# IO.net
KiCad netlist of a schematic drawn in Altium Designer
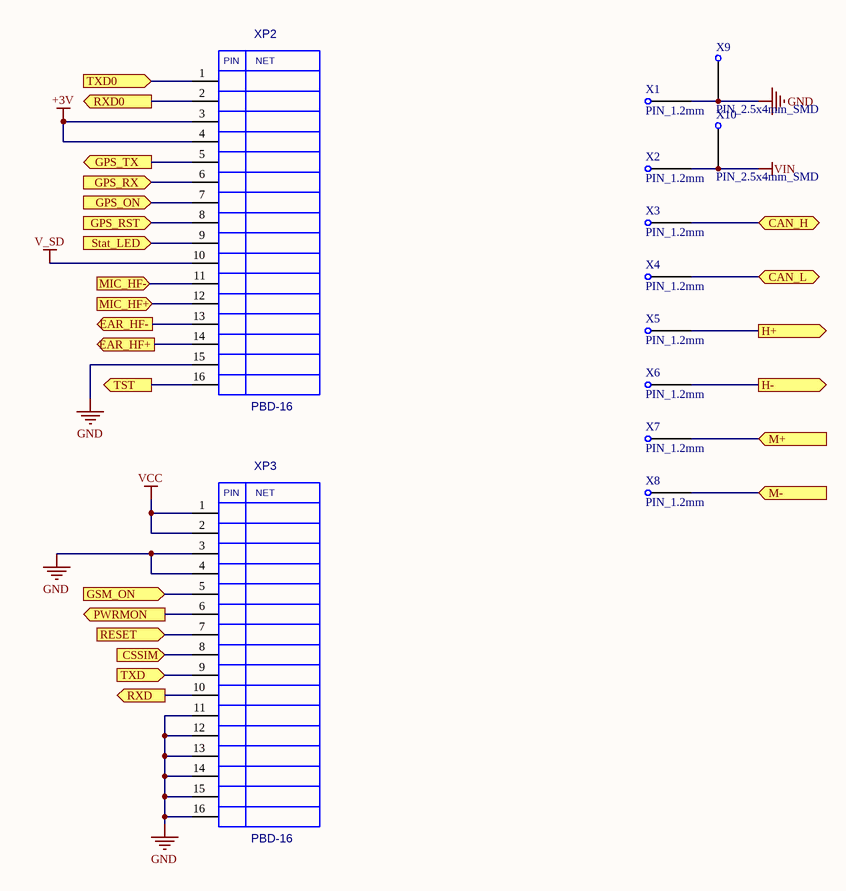
[diagram p0: IO.SchDoc]

(export (version "E")
  (design (tool "Eeschema 10.0.6"))
  (components
    (comp (ref "X1")
      (value "PIN_1.2mm")
      (footprint "PIN_1.2mm")
      (libsource (lib "gprs_modem_2") (part "PIN_1.2mm"))
    )
    (comp (ref "X2")
      (value "PIN_1.2mm")
      (footprint "PIN_1.2mm")
      (libsource (lib "gprs_modem_2") (part "PIN_1.2mm"))
    )
    (comp (ref "X3")
      (value "PIN_1.2mm")
      (footprint "PIN_1.2mm")
      (libsource (lib "gprs_modem_2") (part "PIN_1.2mm"))
    )
    (comp (ref "X4")
      (value "PIN_1.2mm")
      (footprint "PIN_1.2mm")
      (libsource (lib "gprs_modem_2") (part "PIN_1.2mm"))
    )
    (comp (ref "X5")
      (value "PIN_1.2mm")
      (footprint "PIN_1.2mm")
      (libsource (lib "gprs_modem_2") (part "PIN_1.2mm"))
    )
    (comp (ref "X6")
      (value "PIN_1.2mm")
      (footprint "PIN_1.2mm")
      (libsource (lib "gprs_modem_2") (part "PIN_1.2mm"))
    )
    (comp (ref "X7")
      (value "PIN_1.2mm")
      (footprint "PIN_1.2mm")
      (libsource (lib "gprs_modem_2") (part "PIN_1.2mm"))
    )
    (comp (ref "X8")
      (value "PIN_1.2mm")
      (footprint "PIN_1.2mm")
      (libsource (lib "gprs_modem_2") (part "PIN_1.2mm"))
    )
    (comp (ref "X9")
      (value "PIN_2.5x4mm_SMD")
      (footprint "PIN_2.5x4mm_SMD")
      (libsource (lib "gprs_modem_2") (part "PIN_2.5x4mm_SMD"))
    )
    (comp (ref "X10")
      (value "PIN_2.5x4mm_SMD")
      (footprint "PIN_2.5x4mm_SMD")
      (libsource (lib "gprs_modem_2") (part "PIN_2.5x4mm_SMD"))
    )
    (comp (ref "XP2") (value "PBD-16") (footprint "PBD16") (libsource (lib "gprs_modem") (part "PBD-16")))
    (comp (ref "XP3") (value "PBD-16") (footprint "PBD16") (libsource (lib "gprs_modem") (part "PBD-16")))
  )
  (nets
    (net (code "1") (name "+3V") (class "Default")
      (node (ref "XP2") (pin "3") (pinfunction "3_3") (pintype "passive"))
      (node (ref "XP2") (pin "4") (pinfunction "4_4") (pintype "passive"))
    )
    (net (code "2") (name "/CAN_H") (class "Default")
      (node (ref "X3") (pin "1") (pinfunction "1_1") (pintype "passive"))
    )
    (net (code "3") (name "/CAN_L") (class "Default")
      (node (ref "X4") (pin "1") (pinfunction "1_1") (pintype "passive"))
    )
    (net (code "4") (name "/CSSIM") (class "Default")
      (node (ref "XP3") (pin "8") (pinfunction "8_8") (pintype "passive"))
    )
    (net (code "5") (name "/EAR_HF+") (class "Default")
      (node (ref "XP2") (pin "14") (pinfunction "14_14") (pintype "passive"))
    )
    (net (code "6") (name "/EAR_HF-") (class "Default")
      (node (ref "XP2") (pin "13") (pinfunction "13_13") (pintype "passive"))
    )
    (net (code "7") (name "/GPS_ON") (class "Default")
      (node (ref "XP2") (pin "7") (pinfunction "7_7") (pintype "passive"))
    )
    (net (code "8") (name "/GPS_RST") (class "Default")
      (node (ref "XP2") (pin "8") (pinfunction "8_8") (pintype "passive"))
    )
    (net (code "9") (name "/GPS_RX") (class "Default")
      (node (ref "XP2") (pin "6") (pinfunction "6_6") (pintype "passive"))
    )
    (net (code "10") (name "/GPS_TX") (class "Default")
      (node (ref "XP2") (pin "5") (pinfunction "5_5") (pintype "passive"))
    )
    (net (code "11") (name "/GSM_ON") (class "Default")
      (node (ref "XP3") (pin "5") (pinfunction "5_5") (pintype "passive"))
    )
    (net (code "12") (name "/H+") (class "Default")
      (node (ref "X5") (pin "1") (pinfunction "1_1") (pintype "passive"))
    )
    (net (code "13") (name "/H-") (class "Default")
      (node (ref "X6") (pin "1") (pinfunction "1_1") (pintype "passive"))
    )
    (net (code "14") (name "/M+") (class "Default")
      (node (ref "X7") (pin "1") (pinfunction "1_1") (pintype "passive"))
    )
    (net (code "15") (name "/M-") (class "Default")
      (node (ref "X8") (pin "1") (pinfunction "1_1") (pintype "passive"))
    )
    (net (code "16") (name "/MIC_HF+") (class "Default")
      (node (ref "XP2") (pin "12") (pinfunction "12_12") (pintype "passive"))
    )
    (net (code "17") (name "/MIC_HF-") (class "Default")
      (node (ref "XP2") (pin "11") (pinfunction "11_11") (pintype "passive"))
    )
    (net (code "18") (name "/PWRMON") (class "Default")
      (node (ref "XP3") (pin "6") (pinfunction "6_6") (pintype "passive"))
    )
    (net (code "19") (name "/RESET") (class "Default")
      (node (ref "XP3") (pin "7") (pinfunction "7_7") (pintype "passive"))
    )
    (net (code "20") (name "/RXD") (class "Default")
      (node (ref "XP3") (pin "10") (pinfunction "10_10") (pintype "passive"))
    )
    (net (code "21") (name "/RXD0") (class "Default")
      (node (ref "XP2") (pin "2") (pinfunction "2_2") (pintype "passive"))
    )
    (net (code "22") (name "/Stat_LED") (class "Default")
      (node (ref "XP2") (pin "9") (pinfunction "9_9") (pintype "passive"))
    )
    (net (code "23") (name "/TST") (class "Default")
      (node (ref "XP2") (pin "16") (pinfunction "16_16") (pintype "passive"))
    )
    (net (code "24") (name "/TXD") (class "Default")
      (node (ref "XP3") (pin "9") (pinfunction "9_9") (pintype "passive"))
    )
    (net (code "25") (name "/TXD0") (class "Default")
      (node (ref "XP2") (pin "1") (pinfunction "1_1") (pintype "passive"))
    )
    (net (code "26") (name "GND") (class "Default")
      (node (ref "X1") (pin "1") (pinfunction "1_1") (pintype "passive"))
      (node (ref "X9") (pin "1") (pinfunction "1_1") (pintype "passive"))
      (node (ref "XP2") (pin "15") (pinfunction "15_15") (pintype "passive"))
      (node (ref "XP3") (pin "11") (pinfunction "11_11") (pintype "passive"))
      (node (ref "XP3") (pin "12") (pinfunction "12_12") (pintype "passive"))
      (node (ref "XP3") (pin "13") (pinfunction "13_13") (pintype "passive"))
      (node (ref "XP3") (pin "14") (pinfunction "14_14") (pintype "passive"))
      (node (ref "XP3") (pin "15") (pinfunction "15_15") (pintype "passive"))
      (node (ref "XP3") (pin "16") (pinfunction "16_16") (pintype "passive"))
      (node (ref "XP3") (pin "3") (pinfunction "3_3") (pintype "passive"))
      (node (ref "XP3") (pin "4") (pinfunction "4_4") (pintype "passive"))
    )
    (net (code "27") (name "VCC") (class "Default")
      (node (ref "XP3") (pin "1") (pinfunction "1_1") (pintype "passive"))
      (node (ref "XP3") (pin "2") (pinfunction "2_2") (pintype "passive"))
    )
    (net (code "28") (name "VIN") (class "Default")
      (node (ref "X10") (pin "1") (pinfunction "1_1") (pintype "passive"))
      (node (ref "X2") (pin "1") (pinfunction "1_1") (pintype "passive"))
    )
    (net (code "29") (name "V_SD") (class "Default")
      (node (ref "XP2") (pin "10") (pinfunction "10_10") (pintype "passive"))
    )
  )
)
